# 8MBSIMM.net
KiCad netlist of a schematic drawn in EAGLE
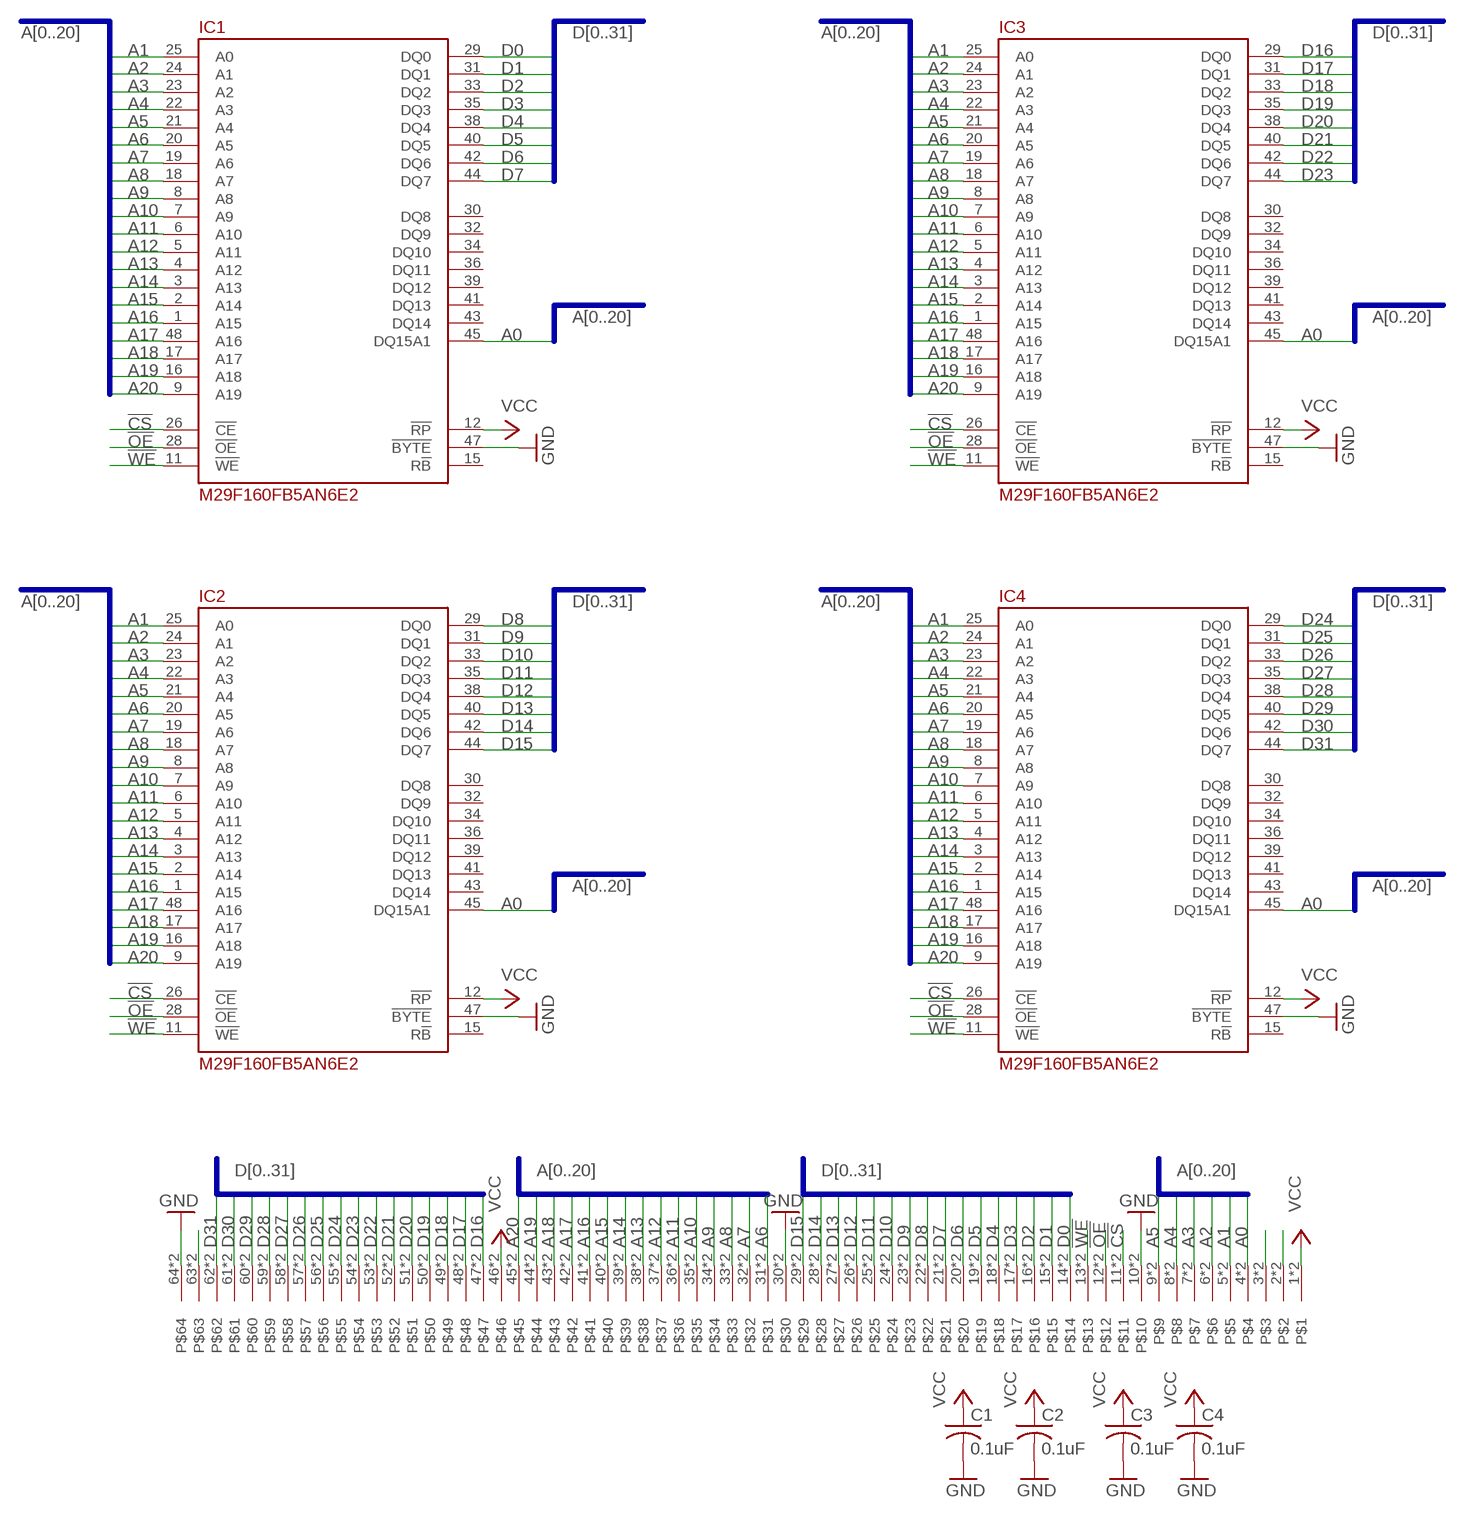
[diagram p0: schematic, sheet 1]

(export (version "E")
  (design (tool "Eeschema 10.0.6"))
  (components
    (comp (ref "C1")
      (value "0.1uF")
      (footprint "eagle-import:C1206")
      (libsource (lib "eagle-import") (part "C-USC1206"))
    )
    (comp (ref "C2")
      (value "0.1uF")
      (footprint "eagle-import:C1206")
      (libsource (lib "eagle-import") (part "C-USC1206"))
    )
    (comp (ref "C3")
      (value "0.1uF")
      (footprint "eagle-import:C1206")
      (libsource (lib "eagle-import") (part "C-USC1206"))
    )
    (comp (ref "C4")
      (value "0.1uF")
      (footprint "eagle-import:C1206")
      (libsource (lib "eagle-import") (part "C-USC1206"))
    )
    (comp (ref "CON1")
      (value "MYSIMM")
      (footprint "eagle-import:SIMM64L")
      (libsource (lib "eagle-import") (part "MYSIMM"))
    )
    (comp (ref "IC1")
      (value "M29F160FB5AN6E2")
      (footprint "eagle-import:TSOP48")
      (libsource (lib "eagle-import") (part "M29F160FB5AN6E2"))
    )
    (comp (ref "IC2")
      (value "M29F160FB5AN6E2")
      (footprint "eagle-import:TSOP48")
      (libsource (lib "eagle-import") (part "M29F160FB5AN6E2"))
    )
    (comp (ref "IC3")
      (value "M29F160FB5AN6E2")
      (footprint "eagle-import:TSOP48")
      (libsource (lib "eagle-import") (part "M29F160FB5AN6E2"))
    )
    (comp (ref "IC4")
      (value "M29F160FB5AN6E2")
      (footprint "eagle-import:TSOP48")
      (libsource (lib "eagle-import") (part "M29F160FB5AN6E2"))
    )
  )
  (nets
    (net (code "1") (name "/A0") (class "Default")
      (node (ref "CON1") (pin "4") (pinfunction "P$4_4") (pintype "bidirectional"))
      (node (ref "CON1") (pin "68") (pinfunction "P$4_68") (pintype "bidirectional"))
      (node (ref "IC1") (pin "45") (pinfunction "DQ15A1_45") (pintype "input"))
      (node (ref "IC2") (pin "45") (pinfunction "DQ15A1_45") (pintype "input"))
      (node (ref "IC3") (pin "45") (pinfunction "DQ15A1_45") (pintype "input"))
      (node (ref "IC4") (pin "45") (pinfunction "DQ15A1_45") (pintype "input"))
    )
    (net (code "2") (name "/A1") (class "Default")
      (node (ref "CON1") (pin "5") (pinfunction "P$5_5") (pintype "bidirectional"))
      (node (ref "CON1") (pin "69") (pinfunction "P$5_69") (pintype "bidirectional"))
      (node (ref "IC1") (pin "25") (pinfunction "A0_25") (pintype "input"))
      (node (ref "IC2") (pin "25") (pinfunction "A0_25") (pintype "input"))
      (node (ref "IC3") (pin "25") (pinfunction "A0_25") (pintype "input"))
      (node (ref "IC4") (pin "25") (pinfunction "A0_25") (pintype "input"))
    )
    (net (code "3") (name "/A2") (class "Default")
      (node (ref "CON1") (pin "6") (pinfunction "P$6_6") (pintype "bidirectional"))
      (node (ref "CON1") (pin "70") (pinfunction "P$6_70") (pintype "bidirectional"))
      (node (ref "IC1") (pin "24") (pinfunction "A1_24") (pintype "input"))
      (node (ref "IC2") (pin "24") (pinfunction "A1_24") (pintype "input"))
      (node (ref "IC3") (pin "24") (pinfunction "A1_24") (pintype "input"))
      (node (ref "IC4") (pin "24") (pinfunction "A1_24") (pintype "input"))
    )
    (net (code "4") (name "/A3") (class "Default")
      (node (ref "CON1") (pin "7") (pinfunction "P$7_7") (pintype "bidirectional"))
      (node (ref "CON1") (pin "71") (pinfunction "P$7_71") (pintype "bidirectional"))
      (node (ref "IC1") (pin "23") (pinfunction "A2_23") (pintype "input"))
      (node (ref "IC2") (pin "23") (pinfunction "A2_23") (pintype "input"))
      (node (ref "IC3") (pin "23") (pinfunction "A2_23") (pintype "input"))
      (node (ref "IC4") (pin "23") (pinfunction "A2_23") (pintype "input"))
    )
    (net (code "5") (name "/A4") (class "Default")
      (node (ref "CON1") (pin "72") (pinfunction "P$8_72") (pintype "bidirectional"))
      (node (ref "CON1") (pin "8") (pinfunction "P$8_8") (pintype "bidirectional"))
      (node (ref "IC1") (pin "22") (pinfunction "A3_22") (pintype "input"))
      (node (ref "IC2") (pin "22") (pinfunction "A3_22") (pintype "input"))
      (node (ref "IC3") (pin "22") (pinfunction "A3_22") (pintype "input"))
      (node (ref "IC4") (pin "22") (pinfunction "A3_22") (pintype "input"))
    )
    (net (code "6") (name "/A5") (class "Default")
      (node (ref "CON1") (pin "73") (pinfunction "P$9_73") (pintype "bidirectional"))
      (node (ref "CON1") (pin "9") (pinfunction "P$9_9") (pintype "bidirectional"))
      (node (ref "IC1") (pin "21") (pinfunction "A4_21") (pintype "input"))
      (node (ref "IC2") (pin "21") (pinfunction "A4_21") (pintype "input"))
      (node (ref "IC3") (pin "21") (pinfunction "A4_21") (pintype "input"))
      (node (ref "IC4") (pin "21") (pinfunction "A4_21") (pintype "input"))
    )
    (net (code "7") (name "/A6") (class "Default")
      (node (ref "CON1") (pin "31") (pinfunction "P$31_31") (pintype "bidirectional"))
      (node (ref "CON1") (pin "95") (pinfunction "P$31_95") (pintype "bidirectional"))
      (node (ref "IC1") (pin "20") (pinfunction "A5_20") (pintype "input"))
      (node (ref "IC2") (pin "20") (pinfunction "A5_20") (pintype "input"))
      (node (ref "IC3") (pin "20") (pinfunction "A5_20") (pintype "input"))
      (node (ref "IC4") (pin "20") (pinfunction "A5_20") (pintype "input"))
    )
    (net (code "8") (name "/A7") (class "Default")
      (node (ref "CON1") (pin "32") (pinfunction "P$32_32") (pintype "bidirectional"))
      (node (ref "CON1") (pin "96") (pinfunction "P$32_96") (pintype "bidirectional"))
      (node (ref "IC1") (pin "19") (pinfunction "A6_19") (pintype "input"))
      (node (ref "IC2") (pin "19") (pinfunction "A6_19") (pintype "input"))
      (node (ref "IC3") (pin "19") (pinfunction "A6_19") (pintype "input"))
      (node (ref "IC4") (pin "19") (pinfunction "A6_19") (pintype "input"))
    )
    (net (code "9") (name "/A8") (class "Default")
      (node (ref "CON1") (pin "33") (pinfunction "P$33_33") (pintype "bidirectional"))
      (node (ref "CON1") (pin "97") (pinfunction "P$33_97") (pintype "bidirectional"))
      (node (ref "IC1") (pin "18") (pinfunction "A7_18") (pintype "input"))
      (node (ref "IC2") (pin "18") (pinfunction "A7_18") (pintype "input"))
      (node (ref "IC3") (pin "18") (pinfunction "A7_18") (pintype "input"))
      (node (ref "IC4") (pin "18") (pinfunction "A7_18") (pintype "input"))
    )
    (net (code "10") (name "/A9") (class "Default")
      (node (ref "CON1") (pin "34") (pinfunction "P$34_34") (pintype "bidirectional"))
      (node (ref "CON1") (pin "98") (pinfunction "P$34_98") (pintype "bidirectional"))
      (node (ref "IC1") (pin "8") (pinfunction "A8_8") (pintype "input"))
      (node (ref "IC2") (pin "8") (pinfunction "A8_8") (pintype "input"))
      (node (ref "IC3") (pin "8") (pinfunction "A8_8") (pintype "input"))
      (node (ref "IC4") (pin "8") (pinfunction "A8_8") (pintype "input"))
    )
    (net (code "11") (name "/A10") (class "Default")
      (node (ref "CON1") (pin "35") (pinfunction "P$35_35") (pintype "bidirectional"))
      (node (ref "CON1") (pin "99") (pinfunction "P$35_99") (pintype "bidirectional"))
      (node (ref "IC1") (pin "7") (pinfunction "A9_7") (pintype "input"))
      (node (ref "IC2") (pin "7") (pinfunction "A9_7") (pintype "input"))
      (node (ref "IC3") (pin "7") (pinfunction "A9_7") (pintype "input"))
      (node (ref "IC4") (pin "7") (pinfunction "A9_7") (pintype "input"))
    )
    (net (code "12") (name "/A11") (class "Default")
      (node (ref "CON1") (pin "100") (pinfunction "P$36_100") (pintype "bidirectional"))
      (node (ref "CON1") (pin "36") (pinfunction "P$36_36") (pintype "bidirectional"))
      (node (ref "IC1") (pin "6") (pinfunction "A10_6") (pintype "input"))
      (node (ref "IC2") (pin "6") (pinfunction "A10_6") (pintype "input"))
      (node (ref "IC3") (pin "6") (pinfunction "A10_6") (pintype "input"))
      (node (ref "IC4") (pin "6") (pinfunction "A10_6") (pintype "input"))
    )
    (net (code "13") (name "/A12") (class "Default")
      (node (ref "CON1") (pin "101") (pinfunction "P$37_101") (pintype "bidirectional"))
      (node (ref "CON1") (pin "37") (pinfunction "P$37_37") (pintype "bidirectional"))
      (node (ref "IC1") (pin "5") (pinfunction "A11_5") (pintype "input"))
      (node (ref "IC2") (pin "5") (pinfunction "A11_5") (pintype "input"))
      (node (ref "IC3") (pin "5") (pinfunction "A11_5") (pintype "input"))
      (node (ref "IC4") (pin "5") (pinfunction "A11_5") (pintype "input"))
    )
    (net (code "14") (name "/A13") (class "Default")
      (node (ref "CON1") (pin "102") (pinfunction "P$38_102") (pintype "bidirectional"))
      (node (ref "CON1") (pin "38") (pinfunction "P$38_38") (pintype "bidirectional"))
      (node (ref "IC1") (pin "4") (pinfunction "A12_4") (pintype "input"))
      (node (ref "IC2") (pin "4") (pinfunction "A12_4") (pintype "input"))
      (node (ref "IC3") (pin "4") (pinfunction "A12_4") (pintype "input"))
      (node (ref "IC4") (pin "4") (pinfunction "A12_4") (pintype "input"))
    )
    (net (code "15") (name "/A14") (class "Default")
      (node (ref "CON1") (pin "103") (pinfunction "P$39_103") (pintype "bidirectional"))
      (node (ref "CON1") (pin "39") (pinfunction "P$39_39") (pintype "bidirectional"))
      (node (ref "IC1") (pin "3") (pinfunction "A13_3") (pintype "input"))
      (node (ref "IC2") (pin "3") (pinfunction "A13_3") (pintype "input"))
      (node (ref "IC3") (pin "3") (pinfunction "A13_3") (pintype "input"))
      (node (ref "IC4") (pin "3") (pinfunction "A13_3") (pintype "input"))
    )
    (net (code "16") (name "/A15") (class "Default")
      (node (ref "CON1") (pin "104") (pinfunction "P$40_104") (pintype "bidirectional"))
      (node (ref "CON1") (pin "40") (pinfunction "P$40_40") (pintype "bidirectional"))
      (node (ref "IC1") (pin "2") (pinfunction "A14_2") (pintype "input"))
      (node (ref "IC2") (pin "2") (pinfunction "A14_2") (pintype "input"))
      (node (ref "IC3") (pin "2") (pinfunction "A14_2") (pintype "input"))
      (node (ref "IC4") (pin "2") (pinfunction "A14_2") (pintype "input"))
    )
    (net (code "17") (name "/A16") (class "Default")
      (node (ref "CON1") (pin "105") (pinfunction "P$41_105") (pintype "bidirectional"))
      (node (ref "CON1") (pin "41") (pinfunction "P$41_41") (pintype "bidirectional"))
      (node (ref "IC1") (pin "1") (pinfunction "A15_1") (pintype "input"))
      (node (ref "IC2") (pin "1") (pinfunction "A15_1") (pintype "input"))
      (node (ref "IC3") (pin "1") (pinfunction "A15_1") (pintype "input"))
      (node (ref "IC4") (pin "1") (pinfunction "A15_1") (pintype "input"))
    )
    (net (code "18") (name "/A17") (class "Default")
      (node (ref "CON1") (pin "106") (pinfunction "P$42_106") (pintype "bidirectional"))
      (node (ref "CON1") (pin "42") (pinfunction "P$42_42") (pintype "bidirectional"))
      (node (ref "IC1") (pin "48") (pinfunction "A16_48") (pintype "input"))
      (node (ref "IC2") (pin "48") (pinfunction "A16_48") (pintype "input"))
      (node (ref "IC3") (pin "48") (pinfunction "A16_48") (pintype "input"))
      (node (ref "IC4") (pin "48") (pinfunction "A16_48") (pintype "input"))
    )
    (net (code "19") (name "/A18") (class "Default")
      (node (ref "CON1") (pin "107") (pinfunction "P$43_107") (pintype "bidirectional"))
      (node (ref "CON1") (pin "43") (pinfunction "P$43_43") (pintype "bidirectional"))
      (node (ref "IC1") (pin "17") (pinfunction "A17_17") (pintype "input"))
      (node (ref "IC2") (pin "17") (pinfunction "A17_17") (pintype "input"))
      (node (ref "IC3") (pin "17") (pinfunction "A17_17") (pintype "input"))
      (node (ref "IC4") (pin "17") (pinfunction "A17_17") (pintype "input"))
    )
    (net (code "20") (name "/A19") (class "Default")
      (node (ref "CON1") (pin "108") (pinfunction "P$44_108") (pintype "bidirectional"))
      (node (ref "CON1") (pin "44") (pinfunction "P$44_44") (pintype "bidirectional"))
      (node (ref "IC1") (pin "16") (pinfunction "A18_16") (pintype "input"))
      (node (ref "IC2") (pin "16") (pinfunction "A18_16") (pintype "input"))
      (node (ref "IC3") (pin "16") (pinfunction "A18_16") (pintype "input"))
      (node (ref "IC4") (pin "16") (pinfunction "A18_16") (pintype "input"))
    )
    (net (code "21") (name "/A20") (class "Default")
      (node (ref "CON1") (pin "109") (pinfunction "P$45_109") (pintype "bidirectional"))
      (node (ref "CON1") (pin "45") (pinfunction "P$45_45") (pintype "bidirectional"))
      (node (ref "IC1") (pin "9") (pinfunction "A19_9") (pintype "input"))
      (node (ref "IC2") (pin "9") (pinfunction "A19_9") (pintype "input"))
      (node (ref "IC3") (pin "9") (pinfunction "A19_9") (pintype "input"))
      (node (ref "IC4") (pin "9") (pinfunction "A19_9") (pintype "input"))
    )
    (net (code "23") (name "/D0") (class "Default")
      (node (ref "CON1") (pin "14") (pinfunction "P$14_14") (pintype "bidirectional"))
      (node (ref "CON1") (pin "78") (pinfunction "P$14_78") (pintype "bidirectional"))
      (node (ref "IC1") (pin "29") (pinfunction "DQ0_29") (pintype "bidirectional"))
    )
    (net (code "24") (name "/D1") (class "Default")
      (node (ref "CON1") (pin "15") (pinfunction "P$15_15") (pintype "bidirectional"))
      (node (ref "CON1") (pin "79") (pinfunction "P$15_79") (pintype "bidirectional"))
      (node (ref "IC1") (pin "31") (pinfunction "DQ1_31") (pintype "bidirectional"))
    )
    (net (code "25") (name "/D2") (class "Default")
      (node (ref "CON1") (pin "16") (pinfunction "P$16_16") (pintype "bidirectional"))
      (node (ref "CON1") (pin "80") (pinfunction "P$16_80") (pintype "bidirectional"))
      (node (ref "IC1") (pin "33") (pinfunction "DQ2_33") (pintype "bidirectional"))
    )
    (net (code "26") (name "/D3") (class "Default")
      (node (ref "CON1") (pin "17") (pinfunction "P$17_17") (pintype "bidirectional"))
      (node (ref "CON1") (pin "81") (pinfunction "P$17_81") (pintype "bidirectional"))
      (node (ref "IC1") (pin "35") (pinfunction "DQ3_35") (pintype "bidirectional"))
    )
    (net (code "27") (name "/D4") (class "Default")
      (node (ref "CON1") (pin "18") (pinfunction "P$18_18") (pintype "bidirectional"))
      (node (ref "CON1") (pin "82") (pinfunction "P$18_82") (pintype "bidirectional"))
      (node (ref "IC1") (pin "38") (pinfunction "DQ4_38") (pintype "bidirectional"))
    )
    (net (code "28") (name "/D5") (class "Default")
      (node (ref "CON1") (pin "19") (pinfunction "P$19_19") (pintype "bidirectional"))
      (node (ref "CON1") (pin "83") (pinfunction "P$19_83") (pintype "bidirectional"))
      (node (ref "IC1") (pin "40") (pinfunction "DQ5_40") (pintype "bidirectional"))
    )
    (net (code "29") (name "/D6") (class "Default")
      (node (ref "CON1") (pin "20") (pinfunction "P$20_20") (pintype "bidirectional"))
      (node (ref "CON1") (pin "84") (pinfunction "P$20_84") (pintype "bidirectional"))
      (node (ref "IC1") (pin "42") (pinfunction "DQ6_42") (pintype "bidirectional"))
    )
    (net (code "30") (name "/D7") (class "Default")
      (node (ref "CON1") (pin "21") (pinfunction "P$21_21") (pintype "bidirectional"))
      (node (ref "CON1") (pin "85") (pinfunction "P$21_85") (pintype "bidirectional"))
      (node (ref "IC1") (pin "44") (pinfunction "DQ7_44") (pintype "bidirectional"))
    )
    (net (code "31") (name "/D8") (class "Default")
      (node (ref "CON1") (pin "22") (pinfunction "P$22_22") (pintype "bidirectional"))
      (node (ref "CON1") (pin "86") (pinfunction "P$22_86") (pintype "bidirectional"))
      (node (ref "IC2") (pin "29") (pinfunction "DQ0_29") (pintype "bidirectional"))
    )
    (net (code "32") (name "/D9") (class "Default")
      (node (ref "CON1") (pin "23") (pinfunction "P$23_23") (pintype "bidirectional"))
      (node (ref "CON1") (pin "87") (pinfunction "P$23_87") (pintype "bidirectional"))
      (node (ref "IC2") (pin "31") (pinfunction "DQ1_31") (pintype "bidirectional"))
    )
    (net (code "33") (name "/D10") (class "Default")
      (node (ref "CON1") (pin "24") (pinfunction "P$24_24") (pintype "bidirectional"))
      (node (ref "CON1") (pin "88") (pinfunction "P$24_88") (pintype "bidirectional"))
      (node (ref "IC2") (pin "33") (pinfunction "DQ2_33") (pintype "bidirectional"))
    )
    (net (code "34") (name "/D11") (class "Default")
      (node (ref "CON1") (pin "25") (pinfunction "P$25_25") (pintype "bidirectional"))
      (node (ref "CON1") (pin "89") (pinfunction "P$25_89") (pintype "bidirectional"))
      (node (ref "IC2") (pin "35") (pinfunction "DQ3_35") (pintype "bidirectional"))
    )
    (net (code "35") (name "/D12") (class "Default")
      (node (ref "CON1") (pin "26") (pinfunction "P$26_26") (pintype "bidirectional"))
      (node (ref "CON1") (pin "90") (pinfunction "P$26_90") (pintype "bidirectional"))
      (node (ref "IC2") (pin "38") (pinfunction "DQ4_38") (pintype "bidirectional"))
    )
    (net (code "36") (name "/D13") (class "Default")
      (node (ref "CON1") (pin "27") (pinfunction "P$27_27") (pintype "bidirectional"))
      (node (ref "CON1") (pin "91") (pinfunction "P$27_91") (pintype "bidirectional"))
      (node (ref "IC2") (pin "40") (pinfunction "DQ5_40") (pintype "bidirectional"))
    )
    (net (code "37") (name "/D14") (class "Default")
      (node (ref "CON1") (pin "28") (pinfunction "P$28_28") (pintype "bidirectional"))
      (node (ref "CON1") (pin "92") (pinfunction "P$28_92") (pintype "bidirectional"))
      (node (ref "IC2") (pin "42") (pinfunction "DQ6_42") (pintype "bidirectional"))
    )
    (net (code "38") (name "/D15") (class "Default")
      (node (ref "CON1") (pin "29") (pinfunction "P$29_29") (pintype "bidirectional"))
      (node (ref "CON1") (pin "93") (pinfunction "P$29_93") (pintype "bidirectional"))
      (node (ref "IC2") (pin "44") (pinfunction "DQ7_44") (pintype "bidirectional"))
    )
    (net (code "39") (name "/D16") (class "Default")
      (node (ref "CON1") (pin "111") (pinfunction "P$47_111") (pintype "bidirectional"))
      (node (ref "CON1") (pin "47") (pinfunction "P$47_47") (pintype "bidirectional"))
      (node (ref "IC3") (pin "29") (pinfunction "DQ0_29") (pintype "bidirectional"))
    )
    (net (code "40") (name "/D17") (class "Default")
      (node (ref "CON1") (pin "112") (pinfunction "P$48_112") (pintype "bidirectional"))
      (node (ref "CON1") (pin "48") (pinfunction "P$48_48") (pintype "bidirectional"))
      (node (ref "IC3") (pin "31") (pinfunction "DQ1_31") (pintype "bidirectional"))
    )
    (net (code "41") (name "/D18") (class "Default")
      (node (ref "CON1") (pin "113") (pinfunction "P$49_113") (pintype "bidirectional"))
      (node (ref "CON1") (pin "49") (pinfunction "P$49_49") (pintype "bidirectional"))
      (node (ref "IC3") (pin "33") (pinfunction "DQ2_33") (pintype "bidirectional"))
    )
    (net (code "42") (name "/D19") (class "Default")
      (node (ref "CON1") (pin "114") (pinfunction "P$50_114") (pintype "bidirectional"))
      (node (ref "CON1") (pin "50") (pinfunction "P$50_50") (pintype "bidirectional"))
      (node (ref "IC3") (pin "35") (pinfunction "DQ3_35") (pintype "bidirectional"))
    )
    (net (code "43") (name "/D20") (class "Default")
      (node (ref "CON1") (pin "115") (pinfunction "P$51_115") (pintype "bidirectional"))
      (node (ref "CON1") (pin "51") (pinfunction "P$51_51") (pintype "bidirectional"))
      (node (ref "IC3") (pin "38") (pinfunction "DQ4_38") (pintype "bidirectional"))
    )
    (net (code "44") (name "/D21") (class "Default")
      (node (ref "CON1") (pin "116") (pinfunction "P$52_116") (pintype "bidirectional"))
      (node (ref "CON1") (pin "52") (pinfunction "P$52_52") (pintype "bidirectional"))
      (node (ref "IC3") (pin "40") (pinfunction "DQ5_40") (pintype "bidirectional"))
    )
    (net (code "45") (name "/D22") (class "Default")
      (node (ref "CON1") (pin "117") (pinfunction "P$53_117") (pintype "bidirectional"))
      (node (ref "CON1") (pin "53") (pinfunction "P$53_53") (pintype "bidirectional"))
      (node (ref "IC3") (pin "42") (pinfunction "DQ6_42") (pintype "bidirectional"))
    )
    (net (code "46") (name "/D23") (class "Default")
      (node (ref "CON1") (pin "118") (pinfunction "P$54_118") (pintype "bidirectional"))
      (node (ref "CON1") (pin "54") (pinfunction "P$54_54") (pintype "bidirectional"))
      (node (ref "IC3") (pin "44") (pinfunction "DQ7_44") (pintype "bidirectional"))
    )
    (net (code "47") (name "/D24") (class "Default")
      (node (ref "CON1") (pin "119") (pinfunction "P$55_119") (pintype "bidirectional"))
      (node (ref "CON1") (pin "55") (pinfunction "P$55_55") (pintype "bidirectional"))
      (node (ref "IC4") (pin "29") (pinfunction "DQ0_29") (pintype "bidirectional"))
    )
    (net (code "48") (name "/D25") (class "Default")
      (node (ref "CON1") (pin "120") (pinfunction "P$56_120") (pintype "bidirectional"))
      (node (ref "CON1") (pin "56") (pinfunction "P$56_56") (pintype "bidirectional"))
      (node (ref "IC4") (pin "31") (pinfunction "DQ1_31") (pintype "bidirectional"))
    )
    (net (code "49") (name "/D26") (class "Default")
      (node (ref "CON1") (pin "121") (pinfunction "P$57_121") (pintype "bidirectional"))
      (node (ref "CON1") (pin "57") (pinfunction "P$57_57") (pintype "bidirectional"))
      (node (ref "IC4") (pin "33") (pinfunction "DQ2_33") (pintype "bidirectional"))
    )
    (net (code "50") (name "/D27") (class "Default")
      (node (ref "CON1") (pin "122") (pinfunction "P$58_122") (pintype "bidirectional"))
      (node (ref "CON1") (pin "58") (pinfunction "P$58_58") (pintype "bidirectional"))
      (node (ref "IC4") (pin "35") (pinfunction "DQ3_35") (pintype "bidirectional"))
    )
    (net (code "51") (name "/D28") (class "Default")
      (node (ref "CON1") (pin "123") (pinfunction "P$59_123") (pintype "bidirectional"))
      (node (ref "CON1") (pin "59") (pinfunction "P$59_59") (pintype "bidirectional"))
      (node (ref "IC4") (pin "38") (pinfunction "DQ4_38") (pintype "bidirectional"))
    )
    (net (code "52") (name "/D29") (class "Default")
      (node (ref "CON1") (pin "124") (pinfunction "P$60_124") (pintype "bidirectional"))
      (node (ref "CON1") (pin "60") (pinfunction "P$60_60") (pintype "bidirectional"))
      (node (ref "IC4") (pin "40") (pinfunction "DQ5_40") (pintype "bidirectional"))
    )
    (net (code "53") (name "/D30") (class "Default")
      (node (ref "CON1") (pin "125") (pinfunction "P$61_125") (pintype "bidirectional"))
      (node (ref "CON1") (pin "61") (pinfunction "P$61_61") (pintype "bidirectional"))
      (node (ref "IC4") (pin "42") (pinfunction "DQ6_42") (pintype "bidirectional"))
    )
    (net (code "54") (name "/D31") (class "Default")
      (node (ref "CON1") (pin "126") (pinfunction "P$62_126") (pintype "bidirectional"))
      (node (ref "CON1") (pin "62") (pinfunction "P$62_62") (pintype "bidirectional"))
      (node (ref "IC4") (pin "44") (pinfunction "DQ7_44") (pintype "bidirectional"))
    )
    (net (code "56") (name "/~{CS}") (class "Default")
      (node (ref "CON1") (pin "11") (pinfunction "P$11_11") (pintype "bidirectional"))
      (node (ref "CON1") (pin "75") (pinfunction "P$11_75") (pintype "bidirectional"))
      (node (ref "IC1") (pin "26") (pinfunction "~{CE}_26") (pintype "input"))
      (node (ref "IC2") (pin "26") (pinfunction "~{CE}_26") (pintype "input"))
      (node (ref "IC3") (pin "26") (pinfunction "~{CE}_26") (pintype "input"))
      (node (ref "IC4") (pin "26") (pinfunction "~{CE}_26") (pintype "input"))
    )
    (net (code "57") (name "/~{OE}") (class "Default")
      (node (ref "CON1") (pin "12") (pinfunction "P$12_12") (pintype "bidirectional"))
      (node (ref "CON1") (pin "76") (pinfunction "P$12_76") (pintype "bidirectional"))
      (node (ref "IC1") (pin "28") (pinfunction "~{OE}_28") (pintype "input"))
      (node (ref "IC2") (pin "28") (pinfunction "~{OE}_28") (pintype "input"))
      (node (ref "IC3") (pin "28") (pinfunction "~{OE}_28") (pintype "input"))
      (node (ref "IC4") (pin "28") (pinfunction "~{OE}_28") (pintype "input"))
    )
    (net (code "58") (name "/~{WE}") (class "Default")
      (node (ref "CON1") (pin "13") (pinfunction "P$13_13") (pintype "bidirectional"))
      (node (ref "CON1") (pin "77") (pinfunction "P$13_77") (pintype "bidirectional"))
      (node (ref "IC1") (pin "11") (pinfunction "~{WE}_11") (pintype "input"))
      (node (ref "IC2") (pin "11") (pinfunction "~{WE}_11") (pintype "input"))
      (node (ref "IC3") (pin "11") (pinfunction "~{WE}_11") (pintype "input"))
      (node (ref "IC4") (pin "11") (pinfunction "~{WE}_11") (pintype "input"))
    )
    (net (code "59") (name "GND") (class "Default")
      (node (ref "C1") (pin "2") (pinfunction "2_2") (pintype "passive"))
      (node (ref "C2") (pin "2") (pinfunction "2_2") (pintype "passive"))
      (node (ref "C3") (pin "2") (pinfunction "2_2") (pintype "passive"))
      (node (ref "C4") (pin "2") (pinfunction "2_2") (pintype "passive"))
      (node (ref "CON1") (pin "10") (pinfunction "P$10_10") (pintype "bidirectional"))
      (node (ref "CON1") (pin "128") (pinfunction "P$64_128") (pintype "bidirectional"))
      (node (ref "CON1") (pin "30") (pinfunction "P$30_30") (pintype "bidirectional"))
      (node (ref "CON1") (pin "64") (pinfunction "P$64_64") (pintype "bidirectional"))
      (node (ref "CON1") (pin "74") (pinfunction "P$10_74") (pintype "bidirectional"))
      (node (ref "CON1") (pin "94") (pinfunction "P$30_94") (pintype "bidirectional"))
      (node (ref "IC1") (pin "47") (pinfunction "~{BYTE}_47") (pintype "input"))
      (node (ref "IC2") (pin "47") (pinfunction "~{BYTE}_47") (pintype "input"))
      (node (ref "IC3") (pin "47") (pinfunction "~{BYTE}_47") (pintype "input"))
      (node (ref "IC4") (pin "47") (pinfunction "~{BYTE}_47") (pintype "input"))
    )
    (net (code "60") (name "Net-(CON1-P$2-Pad2)") (class "Default")
      (node (ref "CON1") (pin "2") (pinfunction "P$2_2") (pintype "bidirectional"))
      (node (ref "CON1") (pin "66") (pinfunction "P$2_66") (pintype "bidirectional"))
    )
    (net (code "61") (name "Net-(CON1-P$3-Pad3)") (class "Default")
      (node (ref "CON1") (pin "3") (pinfunction "P$3_3") (pintype "bidirectional"))
      (node (ref "CON1") (pin "67") (pinfunction "P$3_67") (pintype "bidirectional"))
    )
    (net (code "62") (name "Net-(CON1-P$63-Pad127)") (class "Default")
      (node (ref "CON1") (pin "127") (pinfunction "P$63_127") (pintype "bidirectional"))
      (node (ref "CON1") (pin "63") (pinfunction "P$63_63") (pintype "bidirectional"))
    )
    (net (code "63") (name "VCC") (class "Default")
      (node (ref "C1") (pin "1") (pinfunction "1_1") (pintype "passive"))
      (node (ref "C2") (pin "1") (pinfunction "1_1") (pintype "passive"))
      (node (ref "C3") (pin "1") (pinfunction "1_1") (pintype "passive"))
      (node (ref "C4") (pin "1") (pinfunction "1_1") (pintype "passive"))
      (node (ref "CON1") (pin "1") (pinfunction "P$1_1") (pintype "bidirectional"))
      (node (ref "CON1") (pin "110") (pinfunction "P$46_110") (pintype "bidirectional"))
      (node (ref "CON1") (pin "46") (pinfunction "P$46_46") (pintype "bidirectional"))
      (node (ref "CON1") (pin "65") (pinfunction "P$1_65") (pintype "bidirectional"))
      (node (ref "IC1") (pin "12") (pinfunction "~{RP}_12") (pintype "input"))
      (node (ref "IC2") (pin "12") (pinfunction "~{RP}_12") (pintype "input"))
      (node (ref "IC3") (pin "12") (pinfunction "~{RP}_12") (pintype "input"))
      (node (ref "IC4") (pin "12") (pinfunction "~{RP}_12") (pintype "input"))
    )
    (net (code "64") (name "unconnected-(IC1A-DQ8-Pad30)") (class "Default")
      (node (ref "IC1") (pin "30") (pinfunction "DQ8_30") (pintype "bidirectional"))
    )
    (net (code "65") (name "unconnected-(IC1A-DQ9-Pad32)") (class "Default")
      (node (ref "IC1") (pin "32") (pinfunction "DQ9_32") (pintype "bidirectional"))
    )
    (net (code "66") (name "unconnected-(IC1A-DQ10-Pad34)") (class "Default")
      (node (ref "IC1") (pin "34") (pinfunction "DQ10_34") (pintype "bidirectional"))
    )
    (net (code "67") (name "unconnected-(IC1A-DQ11-Pad36)") (class "Default")
      (node (ref "IC1") (pin "36") (pinfunction "DQ11_36") (pintype "bidirectional"))
    )
    (net (code "68") (name "unconnected-(IC1A-DQ12-Pad39)") (class "Default")
      (node (ref "IC1") (pin "39") (pinfunction "DQ12_39") (pintype "bidirectional"))
    )
    (net (code "69") (name "unconnected-(IC1A-DQ13-Pad41)") (class "Default")
      (node (ref "IC1") (pin "41") (pinfunction "DQ13_41") (pintype "bidirectional"))
    )
    (net (code "70") (name "unconnected-(IC1A-DQ14-Pad43)") (class "Default")
      (node (ref "IC1") (pin "43") (pinfunction "DQ14_43") (pintype "bidirectional"))
    )
    (net (code "71") (name "unconnected-(IC1A-R~{B}-Pad15)") (class "Default")
      (node (ref "IC1") (pin "15") (pinfunction "R~{B}_15") (pintype "output"))
    )
    (net (code "72") (name "unconnected-(IC2A-DQ8-Pad30)") (class "Default")
      (node (ref "IC2") (pin "30") (pinfunction "DQ8_30") (pintype "bidirectional"))
    )
    (net (code "73") (name "unconnected-(IC2A-DQ9-Pad32)") (class "Default")
      (node (ref "IC2") (pin "32") (pinfunction "DQ9_32") (pintype "bidirectional"))
    )
    (net (code "74") (name "unconnected-(IC2A-DQ10-Pad34)") (class "Default")
      (node (ref "IC2") (pin "34") (pinfunction "DQ10_34") (pintype "bidirectional"))
    )
    (net (code "75") (name "unconnected-(IC2A-DQ11-Pad36)") (class "Default")
      (node (ref "IC2") (pin "36") (pinfunction "DQ11_36") (pintype "bidirectional"))
    )
    (net (code "76") (name "unconnected-(IC2A-DQ12-Pad39)") (class "Default")
      (node (ref "IC2") (pin "39") (pinfunction "DQ12_39") (pintype "bidirectional"))
    )
    (net (code "77") (name "unconnected-(IC2A-DQ13-Pad41)") (class "Default")
      (node (ref "IC2") (pin "41") (pinfunction "DQ13_41") (pintype "bidirectional"))
    )
    (net (code "78") (name "unconnected-(IC2A-DQ14-Pad43)") (class "Default")
      (node (ref "IC2") (pin "43") (pinfunction "DQ14_43") (pintype "bidirectional"))
    )
    (net (code "79") (name "unconnected-(IC2A-R~{B}-Pad15)") (class "Default")
      (node (ref "IC2") (pin "15") (pinfunction "R~{B}_15") (pintype "output"))
    )
    (net (code "80") (name "unconnected-(IC3A-DQ8-Pad30)") (class "Default")
      (node (ref "IC3") (pin "30") (pinfunction "DQ8_30") (pintype "bidirectional"))
    )
    (net (code "81") (name "unconnected-(IC3A-DQ9-Pad32)") (class "Default")
      (node (ref "IC3") (pin "32") (pinfunction "DQ9_32") (pintype "bidirectional"))
    )
    (net (code "82") (name "unconnected-(IC3A-DQ10-Pad34)") (class "Default")
      (node (ref "IC3") (pin "34") (pinfunction "DQ10_34") (pintype "bidirectional"))
    )
    (net (code "83") (name "unconnected-(IC3A-DQ11-Pad36)") (class "Default")
      (node (ref "IC3") (pin "36") (pinfunction "DQ11_36") (pintype "bidirectional"))
    )
    (net (code "84") (name "unconnected-(IC3A-DQ12-Pad39)") (class "Default")
      (node (ref "IC3") (pin "39") (pinfunction "DQ12_39") (pintype "bidirectional"))
    )
    (net (code "85") (name "unconnected-(IC3A-DQ13-Pad41)") (class "Default")
      (node (ref "IC3") (pin "41") (pinfunction "DQ13_41") (pintype "bidirectional"))
    )
    (net (code "86") (name "unconnected-(IC3A-DQ14-Pad43)") (class "Default")
      (node (ref "IC3") (pin "43") (pinfunction "DQ14_43") (pintype "bidirectional"))
    )
    (net (code "87") (name "unconnected-(IC3A-R~{B}-Pad15)") (class "Default")
      (node (ref "IC3") (pin "15") (pinfunction "R~{B}_15") (pintype "output"))
    )
    (net (code "88") (name "unconnected-(IC4A-DQ8-Pad30)") (class "Default")
      (node (ref "IC4") (pin "30") (pinfunction "DQ8_30") (pintype "bidirectional"))
    )
    (net (code "89") (name "unconnected-(IC4A-DQ9-Pad32)") (class "Default")
      (node (ref "IC4") (pin "32") (pinfunction "DQ9_32") (pintype "bidirectional"))
    )
    (net (code "90") (name "unconnected-(IC4A-DQ10-Pad34)") (class "Default")
      (node (ref "IC4") (pin "34") (pinfunction "DQ10_34") (pintype "bidirectional"))
    )
    (net (code "91") (name "unconnected-(IC4A-DQ11-Pad36)") (class "Default")
      (node (ref "IC4") (pin "36") (pinfunction "DQ11_36") (pintype "bidirectional"))
    )
    (net (code "92") (name "unconnected-(IC4A-DQ12-Pad39)") (class "Default")
      (node (ref "IC4") (pin "39") (pinfunction "DQ12_39") (pintype "bidirectional"))
    )
    (net (code "93") (name "unconnected-(IC4A-DQ13-Pad41)") (class "Default")
      (node (ref "IC4") (pin "41") (pinfunction "DQ13_41") (pintype "bidirectional"))
    )
    (net (code "94") (name "unconnected-(IC4A-DQ14-Pad43)") (class "Default")
      (node (ref "IC4") (pin "43") (pinfunction "DQ14_43") (pintype "bidirectional"))
    )
    (net (code "95") (name "unconnected-(IC4A-R~{B}-Pad15)") (class "Default")
      (node (ref "IC4") (pin "15") (pinfunction "R~{B}_15") (pintype "output"))
    )
  )
)
